# TriggerTrap_User_Interface_0v39_Release.net
KiCad netlist of a schematic drawn in EAGLE
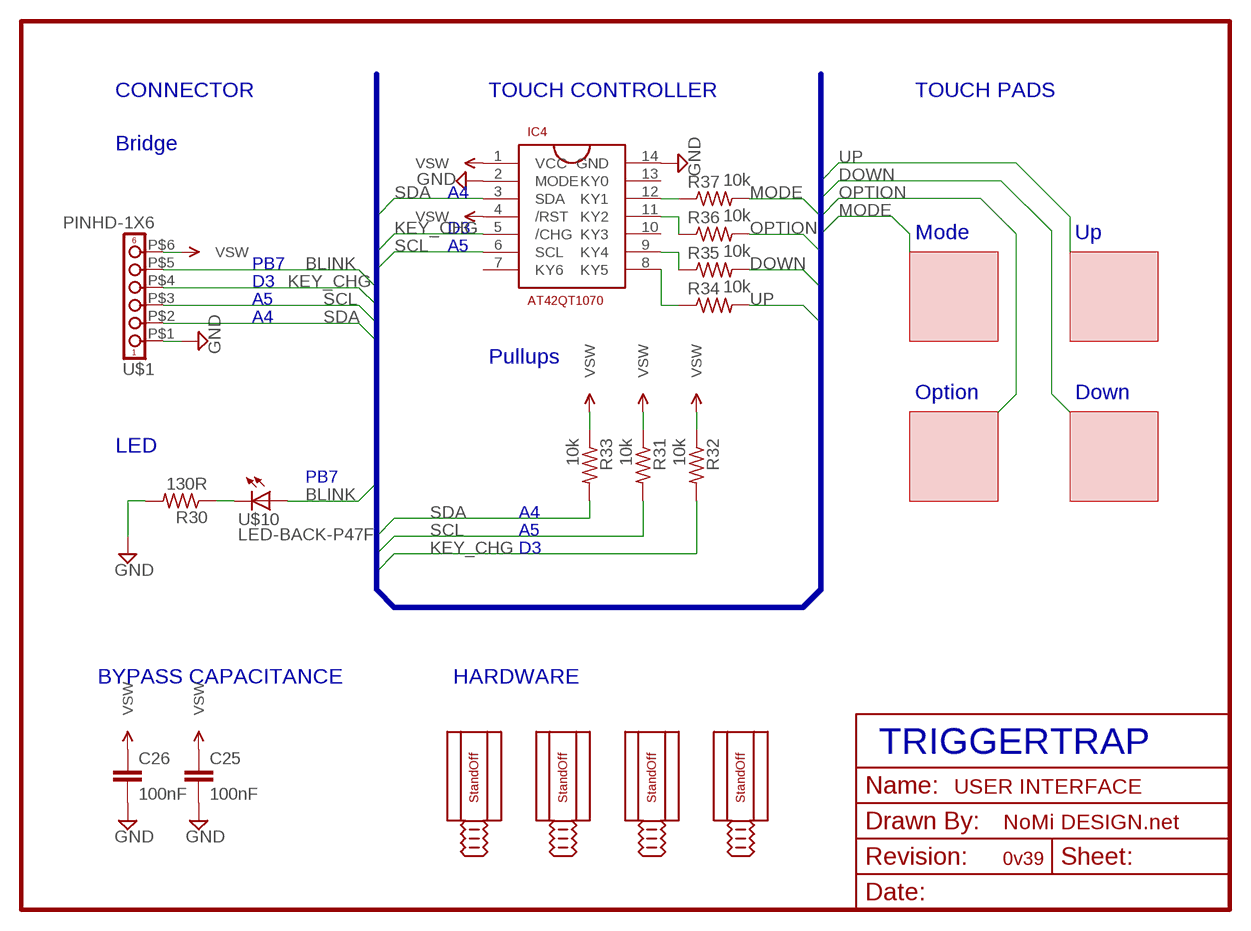
[diagram p0: schematic, sheet 1]

(export (version "E")
  (design (tool "Eeschema 10.0.6"))
  (components
    (comp (ref "C25")
      (value "100nF")
      (footprint "eagle-import:C0603K")
      (libsource (lib "eagle-import") (part "C-EUC0603K"))
    )
    (comp (ref "C26")
      (value "100nF")
      (footprint "eagle-import:C0603K")
      (libsource (lib "eagle-import") (part "C-EUC0603K"))
    )
    (comp (ref "IC4")
      (value "AT42QT1070")
      (footprint "eagle-import:14SOIC")
      (libsource (lib "eagle-import") (part "AT42QT1070"))
    )
    (comp (ref "R30")
      (value "130R")
      (footprint "eagle-import:R0603")
      (libsource (lib "eagle-import") (part "R-US_R0603"))
    )
    (comp (ref "R31")
      (value "10k")
      (footprint "eagle-import:R0603")
      (libsource (lib "eagle-import") (part "R-US_R0603"))
    )
    (comp (ref "R32")
      (value "10k")
      (footprint "eagle-import:R0603")
      (libsource (lib "eagle-import") (part "R-US_R0603"))
    )
    (comp (ref "R33")
      (value "10k")
      (footprint "eagle-import:R0603")
      (libsource (lib "eagle-import") (part "R-US_R0603"))
    )
    (comp (ref "R34")
      (value "10k")
      (footprint "eagle-import:R0603")
      (libsource (lib "eagle-import") (part "R-US_R0603"))
    )
    (comp (ref "R35")
      (value "10k")
      (footprint "eagle-import:R0603")
      (libsource (lib "eagle-import") (part "R-US_R0603"))
    )
    (comp (ref "R36")
      (value "10k")
      (footprint "eagle-import:R0603")
      (libsource (lib "eagle-import") (part "R-US_R0603"))
    )
    (comp (ref "R37")
      (value "10k")
      (footprint "eagle-import:R0603")
      (libsource (lib "eagle-import") (part "R-US_R0603"))
    )
    (comp (ref "U$1")
      (value "PINHD-1X6")
      (footprint "eagle-import:PINHD-1X6-SMD")
      (libsource (lib "eagle-import") (part "PINHD-1X6"))
    )
    (comp (ref "U$2")
      (value "STAND-0FF-3.2")
      (footprint "eagle-import:STAND-OFF")
      (libsource (lib "eagle-import") (part "STAND-0FF-3.2"))
    )
    (comp (ref "U$10")
      (value "LED-BACK-P47F")
      (footprint "eagle-import:LED-P47F")
      (libsource (lib "eagle-import") (part "LED-BACK-P47F"))
    )
    (comp (ref "U$23")
      (value "STAND-0FF-3.2")
      (footprint "eagle-import:STAND-OFF")
      (libsource (lib "eagle-import") (part "STAND-0FF-3.2"))
    )
    (comp (ref "U$24")
      (value "STAND-0FF-3.2")
      (footprint "eagle-import:STAND-OFF")
      (libsource (lib "eagle-import") (part "STAND-0FF-3.2"))
    )
    (comp (ref "U$25")
      (value "STAND-0FF-3.2")
      (footprint "eagle-import:STAND-OFF")
      (libsource (lib "eagle-import") (part "STAND-0FF-3.2"))
    )
  )
  (nets
    (net (code "1") (name "/BLINK") (class "Default")
      (node (ref "U$1") (pin "P$5") (pinfunction "5_P$5") (pintype "passive"))
      (node (ref "U$10") (pin "A") (pinfunction "A_A") (pintype "passive"))
    )
    (net (code "2") (name "/DOWN") (class "Default")
      (node (ref "R35") (pin "2") (pinfunction "2_2") (pintype "passive"))
    )
    (net (code "3") (name "/KEY_CHG") (class "Default")
      (node (ref "IC4") (pin "5") (pinfunction "/CHG_5") (pintype "bidirectional"))
      (node (ref "R32") (pin "2") (pinfunction "2_2") (pintype "passive"))
      (node (ref "U$1") (pin "P$4") (pinfunction "4_P$4") (pintype "passive"))
    )
    (net (code "4") (name "/MODE") (class "Default")
      (node (ref "R37") (pin "2") (pinfunction "2_2") (pintype "passive"))
    )
    (net (code "5") (name "/OPTION") (class "Default")
      (node (ref "R36") (pin "2") (pinfunction "2_2") (pintype "passive"))
    )
    (net (code "6") (name "/SCL") (class "Default")
      (node (ref "IC4") (pin "6") (pinfunction "SCL_6") (pintype "bidirectional"))
      (node (ref "R31") (pin "2") (pinfunction "2_2") (pintype "passive"))
      (node (ref "U$1") (pin "P$3") (pinfunction "3_P$3") (pintype "passive"))
    )
    (net (code "7") (name "/SDA") (class "Default")
      (node (ref "IC4") (pin "3") (pinfunction "SDA_3") (pintype "bidirectional"))
      (node (ref "R33") (pin "2") (pinfunction "2_2") (pintype "passive"))
      (node (ref "U$1") (pin "P$2") (pinfunction "2_P$2") (pintype "passive"))
    )
    (net (code "8") (name "/UP") (class "Default")
      (node (ref "R34") (pin "2") (pinfunction "2_2") (pintype "passive"))
    )
    (net (code "9") (name "GND") (class "Default")
      (node (ref "C25") (pin "2") (pinfunction "2_2") (pintype "passive"))
      (node (ref "C26") (pin "2") (pinfunction "2_2") (pintype "passive"))
      (node (ref "IC4") (pin "14") (pinfunction "GND_14") (pintype "bidirectional"))
      (node (ref "IC4") (pin "2") (pinfunction "MODE_2") (pintype "bidirectional"))
      (node (ref "R30") (pin "2") (pinfunction "2_2") (pintype "passive"))
      (node (ref "U$1") (pin "P$1") (pinfunction "1_P$1") (pintype "passive"))
    )
    (net (code "10") (name "Net-(IC4-KY1)") (class "Default")
      (node (ref "IC4") (pin "12") (pinfunction "KY1_12") (pintype "bidirectional"))
      (node (ref "R37") (pin "1") (pinfunction "1_1") (pintype "passive"))
    )
    (net (code "11") (name "Net-(IC4-KY2)") (class "Default")
      (node (ref "IC4") (pin "11") (pinfunction "KY2_11") (pintype "bidirectional"))
      (node (ref "R36") (pin "1") (pinfunction "1_1") (pintype "passive"))
    )
    (net (code "12") (name "Net-(IC4-KY4)") (class "Default")
      (node (ref "IC4") (pin "9") (pinfunction "KY4_9") (pintype "bidirectional"))
      (node (ref "R35") (pin "1") (pinfunction "1_1") (pintype "passive"))
    )
    (net (code "13") (name "Net-(IC4-KY5)") (class "Default")
      (node (ref "IC4") (pin "8") (pinfunction "KY5_8") (pintype "bidirectional"))
      (node (ref "R34") (pin "1") (pinfunction "1_1") (pintype "passive"))
    )
    (net (code "14") (name "Net-(R30-Pad1)") (class "Default")
      (node (ref "R30") (pin "1") (pinfunction "1_1") (pintype "passive"))
      (node (ref "U$10") (pin "C") (pinfunction "C_C") (pintype "passive"))
    )
    (net (code "15") (name "VSW") (class "Default")
      (node (ref "C25") (pin "1") (pinfunction "1_1") (pintype "passive"))
      (node (ref "C26") (pin "1") (pinfunction "1_1") (pintype "passive"))
      (node (ref "IC4") (pin "1") (pinfunction "VCC_1") (pintype "bidirectional"))
      (node (ref "IC4") (pin "4") (pinfunction "/RST_4") (pintype "bidirectional"))
      (node (ref "R31") (pin "1") (pinfunction "1_1") (pintype "passive"))
      (node (ref "R32") (pin "1") (pinfunction "1_1") (pintype "passive"))
      (node (ref "R33") (pin "1") (pinfunction "1_1") (pintype "passive"))
      (node (ref "U$1") (pin "P$6") (pinfunction "6_P$6") (pintype "passive"))
    )
    (net (code "16") (name "unconnected-(IC4-KY0-Pad13)") (class "Default")
      (node (ref "IC4") (pin "13") (pinfunction "KY0_13") (pintype "bidirectional"))
    )
    (net (code "17") (name "unconnected-(IC4-KY3-Pad10)") (class "Default")
      (node (ref "IC4") (pin "10") (pinfunction "KY3_10") (pintype "bidirectional"))
    )
    (net (code "18") (name "unconnected-(IC4-KY6-Pad7)") (class "Default")
      (node (ref "IC4") (pin "7") (pinfunction "KY6_7") (pintype "bidirectional"))
    )
  )
)
